# KallaxScreen.net
KiCad netlist of a schematic drawn in EAGLE
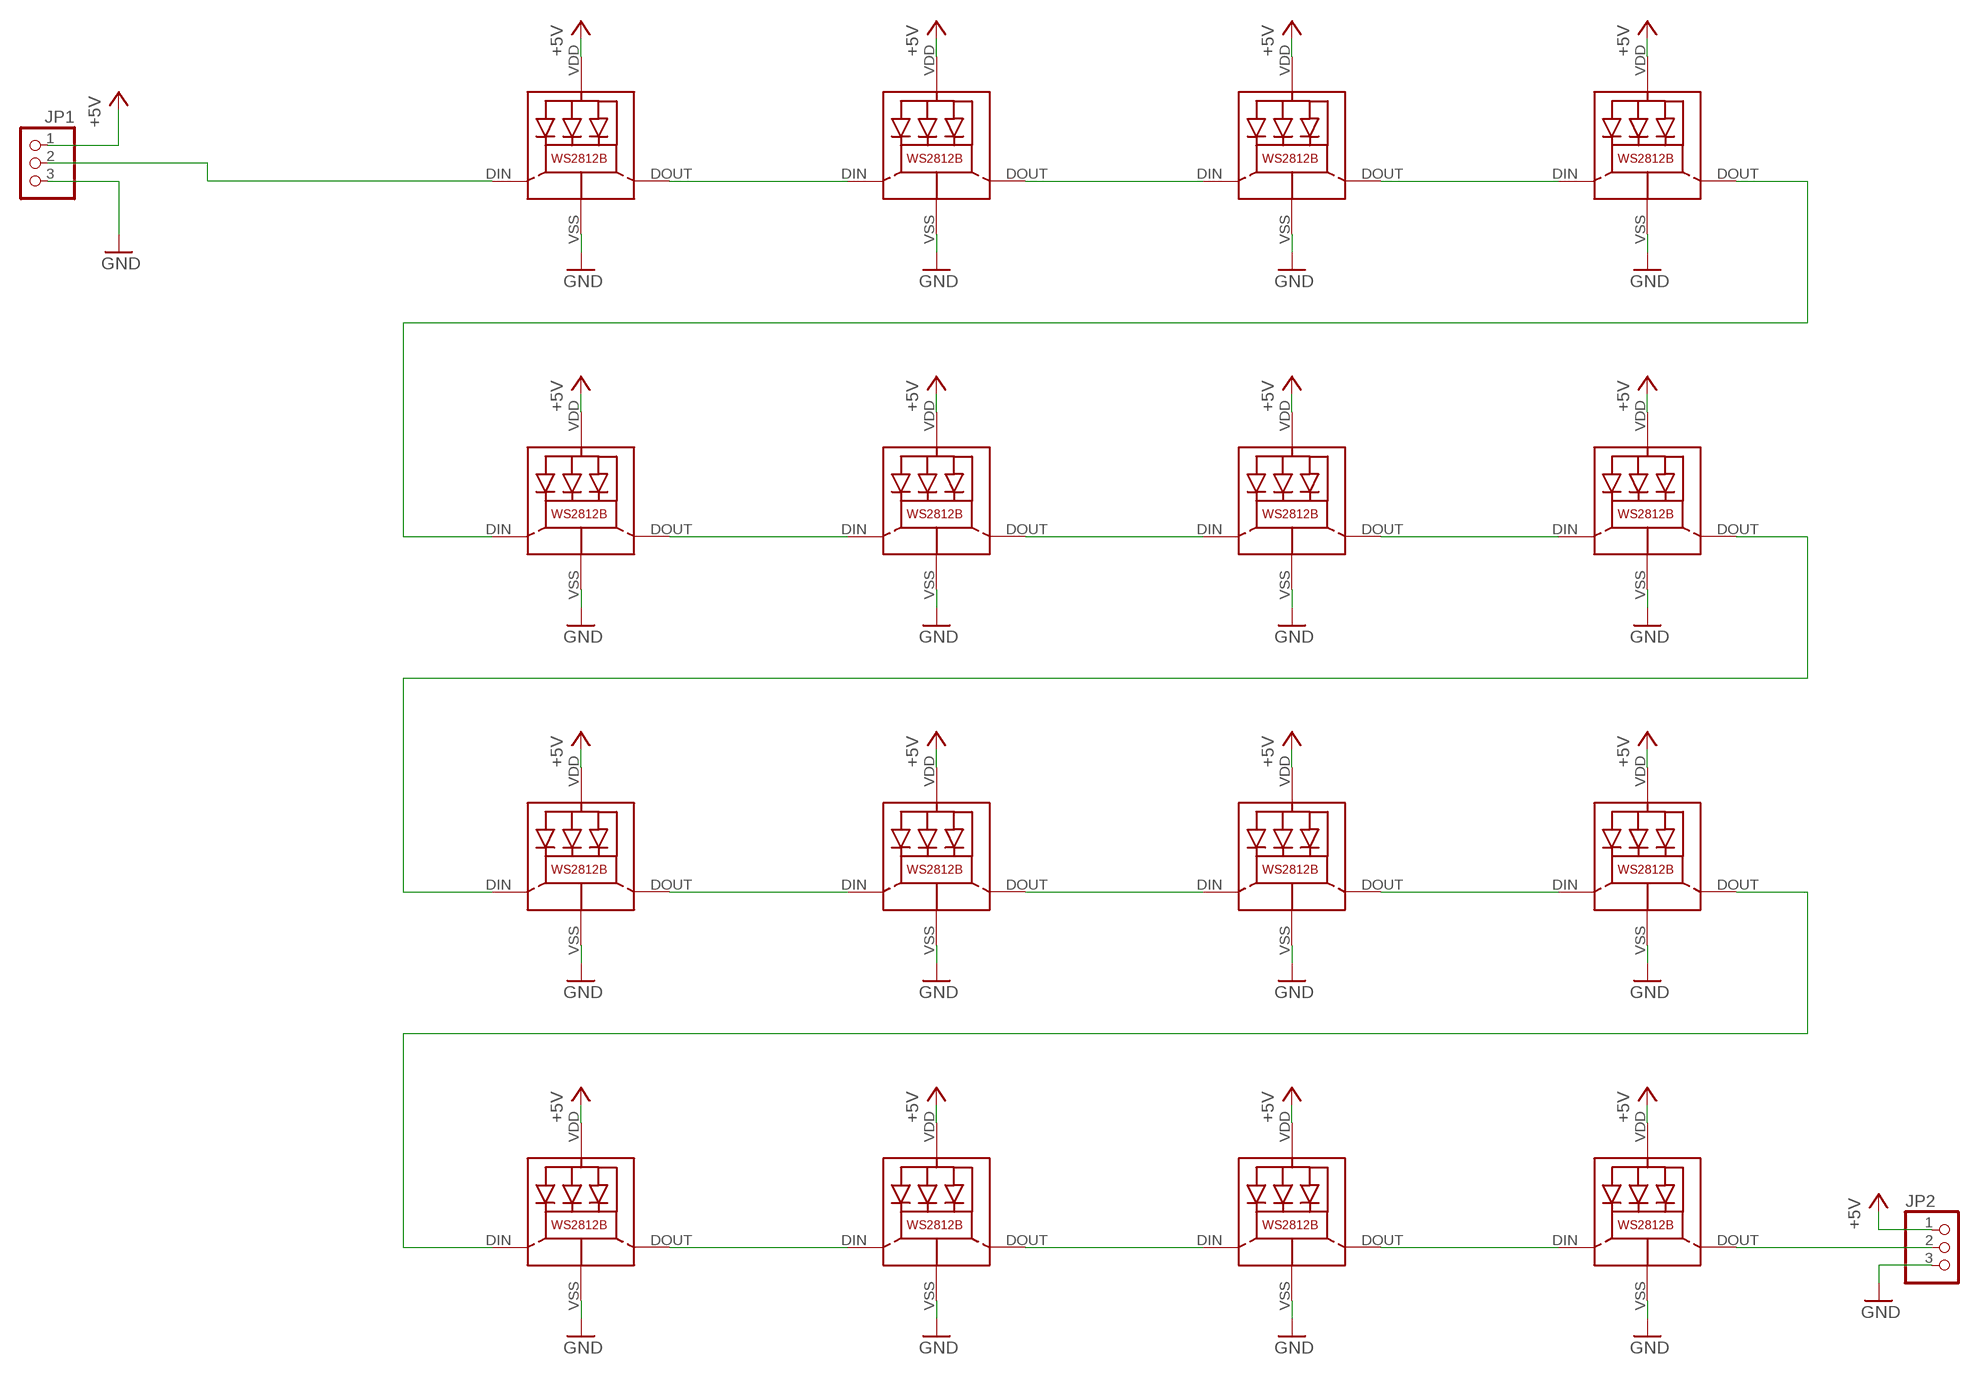
[diagram p0: schematic, sheet 1]

(export (version "E")
  (design (tool "Eeschema 10.0.6"))
  (components
    (comp (ref "JP1")
      (value "PINHD-1X3")
      (footprint "eagle-import:1X03")
      (libsource (lib "eagle-import") (part "PINHD-1X3"))
    )
    (comp (ref "JP2")
      (value "PINHD-1X3")
      (footprint "eagle-import:1X03")
      (libsource (lib "eagle-import") (part "PINHD-1X3"))
    )
    (comp (ref "LED1")
      (value "WS2812B")
      (footprint "eagle-import:WS2812B")
      (libsource (lib "eagle-import") (part "WS2812B"))
    )
    (comp (ref "LED2")
      (value "WS2812B")
      (footprint "eagle-import:WS2812B")
      (libsource (lib "eagle-import") (part "WS2812B"))
    )
    (comp (ref "LED3")
      (value "WS2812B")
      (footprint "eagle-import:WS2812B")
      (libsource (lib "eagle-import") (part "WS2812B"))
    )
    (comp (ref "LED4")
      (value "WS2812B")
      (footprint "eagle-import:WS2812B")
      (libsource (lib "eagle-import") (part "WS2812B"))
    )
    (comp (ref "LED5")
      (value "WS2812B")
      (footprint "eagle-import:WS2812B")
      (libsource (lib "eagle-import") (part "WS2812B"))
    )
    (comp (ref "LED6")
      (value "WS2812B")
      (footprint "eagle-import:WS2812B")
      (libsource (lib "eagle-import") (part "WS2812B"))
    )
    (comp (ref "LED7")
      (value "WS2812B")
      (footprint "eagle-import:WS2812B")
      (libsource (lib "eagle-import") (part "WS2812B"))
    )
    (comp (ref "LED8")
      (value "WS2812B")
      (footprint "eagle-import:WS2812B")
      (libsource (lib "eagle-import") (part "WS2812B"))
    )
    (comp (ref "LED9")
      (value "WS2812B")
      (footprint "eagle-import:WS2812B")
      (libsource (lib "eagle-import") (part "WS2812B"))
    )
    (comp (ref "LED10")
      (value "WS2812B")
      (footprint "eagle-import:WS2812B")
      (libsource (lib "eagle-import") (part "WS2812B"))
    )
    (comp (ref "LED11")
      (value "WS2812B")
      (footprint "eagle-import:WS2812B")
      (libsource (lib "eagle-import") (part "WS2812B"))
    )
    (comp (ref "LED12")
      (value "WS2812B")
      (footprint "eagle-import:WS2812B")
      (libsource (lib "eagle-import") (part "WS2812B"))
    )
    (comp (ref "LED13")
      (value "WS2812B")
      (footprint "eagle-import:WS2812B")
      (libsource (lib "eagle-import") (part "WS2812B"))
    )
    (comp (ref "LED14")
      (value "WS2812B")
      (footprint "eagle-import:WS2812B")
      (libsource (lib "eagle-import") (part "WS2812B"))
    )
    (comp (ref "LED15")
      (value "WS2812B")
      (footprint "eagle-import:WS2812B")
      (libsource (lib "eagle-import") (part "WS2812B"))
    )
    (comp (ref "LED16")
      (value "WS2812B")
      (footprint "eagle-import:WS2812B")
      (libsource (lib "eagle-import") (part "WS2812B"))
    )
  )
  (nets
    (net (code "1") (name "+5V") (class "Default")
      (node (ref "JP1") (pin "1") (pinfunction "1_1") (pintype "passive"))
      (node (ref "JP2") (pin "1") (pinfunction "1_1") (pintype "passive"))
      (node (ref "LED1") (pin "VDD") (pinfunction "VDD_VDD") (pintype "power_in"))
      (node (ref "LED10") (pin "VDD") (pinfunction "VDD_VDD") (pintype "power_in"))
      (node (ref "LED11") (pin "VDD") (pinfunction "VDD_VDD") (pintype "power_in"))
      (node (ref "LED12") (pin "VDD") (pinfunction "VDD_VDD") (pintype "power_in"))
      (node (ref "LED13") (pin "VDD") (pinfunction "VDD_VDD") (pintype "power_in"))
      (node (ref "LED14") (pin "VDD") (pinfunction "VDD_VDD") (pintype "power_in"))
      (node (ref "LED15") (pin "VDD") (pinfunction "VDD_VDD") (pintype "power_in"))
      (node (ref "LED16") (pin "VDD") (pinfunction "VDD_VDD") (pintype "power_in"))
      (node (ref "LED2") (pin "VDD") (pinfunction "VDD_VDD") (pintype "power_in"))
      (node (ref "LED3") (pin "VDD") (pinfunction "VDD_VDD") (pintype "power_in"))
      (node (ref "LED4") (pin "VDD") (pinfunction "VDD_VDD") (pintype "power_in"))
      (node (ref "LED5") (pin "VDD") (pinfunction "VDD_VDD") (pintype "power_in"))
      (node (ref "LED6") (pin "VDD") (pinfunction "VDD_VDD") (pintype "power_in"))
      (node (ref "LED7") (pin "VDD") (pinfunction "VDD_VDD") (pintype "power_in"))
      (node (ref "LED8") (pin "VDD") (pinfunction "VDD_VDD") (pintype "power_in"))
      (node (ref "LED9") (pin "VDD") (pinfunction "VDD_VDD") (pintype "power_in"))
    )
    (net (code "2") (name "GND") (class "Default")
      (node (ref "JP1") (pin "3") (pinfunction "3_3") (pintype "passive"))
      (node (ref "JP2") (pin "3") (pinfunction "3_3") (pintype "passive"))
      (node (ref "LED1") (pin "VSS") (pinfunction "GND_VSS") (pintype "power_in"))
      (node (ref "LED10") (pin "VSS") (pinfunction "GND_VSS") (pintype "power_in"))
      (node (ref "LED11") (pin "VSS") (pinfunction "GND_VSS") (pintype "power_in"))
      (node (ref "LED12") (pin "VSS") (pinfunction "GND_VSS") (pintype "power_in"))
      (node (ref "LED13") (pin "VSS") (pinfunction "GND_VSS") (pintype "power_in"))
      (node (ref "LED14") (pin "VSS") (pinfunction "GND_VSS") (pintype "power_in"))
      (node (ref "LED15") (pin "VSS") (pinfunction "GND_VSS") (pintype "power_in"))
      (node (ref "LED16") (pin "VSS") (pinfunction "GND_VSS") (pintype "power_in"))
      (node (ref "LED2") (pin "VSS") (pinfunction "GND_VSS") (pintype "power_in"))
      (node (ref "LED3") (pin "VSS") (pinfunction "GND_VSS") (pintype "power_in"))
      (node (ref "LED4") (pin "VSS") (pinfunction "GND_VSS") (pintype "power_in"))
      (node (ref "LED5") (pin "VSS") (pinfunction "GND_VSS") (pintype "power_in"))
      (node (ref "LED6") (pin "VSS") (pinfunction "GND_VSS") (pintype "power_in"))
      (node (ref "LED7") (pin "VSS") (pinfunction "GND_VSS") (pintype "power_in"))
      (node (ref "LED8") (pin "VSS") (pinfunction "GND_VSS") (pintype "power_in"))
      (node (ref "LED9") (pin "VSS") (pinfunction "GND_VSS") (pintype "power_in"))
    )
    (net (code "3") (name "Net-(LED1-DI)") (class "Default")
      (node (ref "JP1") (pin "2") (pinfunction "2_2") (pintype "passive"))
      (node (ref "LED1") (pin "DIN") (pinfunction "DI_DIN") (pintype "input"))
    )
    (net (code "4") (name "Net-(LED1-DO)") (class "Default")
      (node (ref "LED1") (pin "DOUT") (pinfunction "DO_DOUT") (pintype "output"))
      (node (ref "LED2") (pin "DIN") (pinfunction "DI_DIN") (pintype "input"))
    )
    (net (code "5") (name "Net-(LED2-DO)") (class "Default")
      (node (ref "LED2") (pin "DOUT") (pinfunction "DO_DOUT") (pintype "output"))
      (node (ref "LED3") (pin "DIN") (pinfunction "DI_DIN") (pintype "input"))
    )
    (net (code "6") (name "Net-(LED3-DO)") (class "Default")
      (node (ref "LED3") (pin "DOUT") (pinfunction "DO_DOUT") (pintype "output"))
      (node (ref "LED4") (pin "DIN") (pinfunction "DI_DIN") (pintype "input"))
    )
    (net (code "7") (name "Net-(LED4-DO)") (class "Default")
      (node (ref "LED4") (pin "DOUT") (pinfunction "DO_DOUT") (pintype "output"))
      (node (ref "LED5") (pin "DIN") (pinfunction "DI_DIN") (pintype "input"))
    )
    (net (code "8") (name "Net-(LED5-DO)") (class "Default")
      (node (ref "LED5") (pin "DOUT") (pinfunction "DO_DOUT") (pintype "output"))
      (node (ref "LED6") (pin "DIN") (pinfunction "DI_DIN") (pintype "input"))
    )
    (net (code "9") (name "Net-(LED6-DO)") (class "Default")
      (node (ref "LED6") (pin "DOUT") (pinfunction "DO_DOUT") (pintype "output"))
      (node (ref "LED7") (pin "DIN") (pinfunction "DI_DIN") (pintype "input"))
    )
    (net (code "10") (name "Net-(LED7-DO)") (class "Default")
      (node (ref "LED7") (pin "DOUT") (pinfunction "DO_DOUT") (pintype "output"))
      (node (ref "LED8") (pin "DIN") (pinfunction "DI_DIN") (pintype "input"))
    )
    (net (code "11") (name "Net-(LED8-DO)") (class "Default")
      (node (ref "LED8") (pin "DOUT") (pinfunction "DO_DOUT") (pintype "output"))
      (node (ref "LED9") (pin "DIN") (pinfunction "DI_DIN") (pintype "input"))
    )
    (net (code "12") (name "Net-(LED10-DI)") (class "Default")
      (node (ref "LED10") (pin "DIN") (pinfunction "DI_DIN") (pintype "input"))
      (node (ref "LED9") (pin "DOUT") (pinfunction "DO_DOUT") (pintype "output"))
    )
    (net (code "13") (name "Net-(LED10-DO)") (class "Default")
      (node (ref "LED10") (pin "DOUT") (pinfunction "DO_DOUT") (pintype "output"))
      (node (ref "LED11") (pin "DIN") (pinfunction "DI_DIN") (pintype "input"))
    )
    (net (code "14") (name "Net-(LED11-DO)") (class "Default")
      (node (ref "LED11") (pin "DOUT") (pinfunction "DO_DOUT") (pintype "output"))
      (node (ref "LED12") (pin "DIN") (pinfunction "DI_DIN") (pintype "input"))
    )
    (net (code "15") (name "Net-(LED12-DO)") (class "Default")
      (node (ref "LED12") (pin "DOUT") (pinfunction "DO_DOUT") (pintype "output"))
      (node (ref "LED13") (pin "DIN") (pinfunction "DI_DIN") (pintype "input"))
    )
    (net (code "16") (name "Net-(LED13-DO)") (class "Default")
      (node (ref "LED13") (pin "DOUT") (pinfunction "DO_DOUT") (pintype "output"))
      (node (ref "LED14") (pin "DIN") (pinfunction "DI_DIN") (pintype "input"))
    )
    (net (code "17") (name "Net-(LED14-DO)") (class "Default")
      (node (ref "LED14") (pin "DOUT") (pinfunction "DO_DOUT") (pintype "output"))
      (node (ref "LED15") (pin "DIN") (pinfunction "DI_DIN") (pintype "input"))
    )
    (net (code "18") (name "Net-(LED15-DO)") (class "Default")
      (node (ref "LED15") (pin "DOUT") (pinfunction "DO_DOUT") (pintype "output"))
      (node (ref "LED16") (pin "DIN") (pinfunction "DI_DIN") (pintype "input"))
    )
    (net (code "19") (name "Net-(LED16-DO)") (class "Default")
      (node (ref "JP2") (pin "2") (pinfunction "2_2") (pintype "passive"))
      (node (ref "LED16") (pin "DOUT") (pinfunction "DO_DOUT") (pintype "output"))
    )
  )
)
